# gl-gps.net
KiCad netlist of a schematic drawn in EAGLE
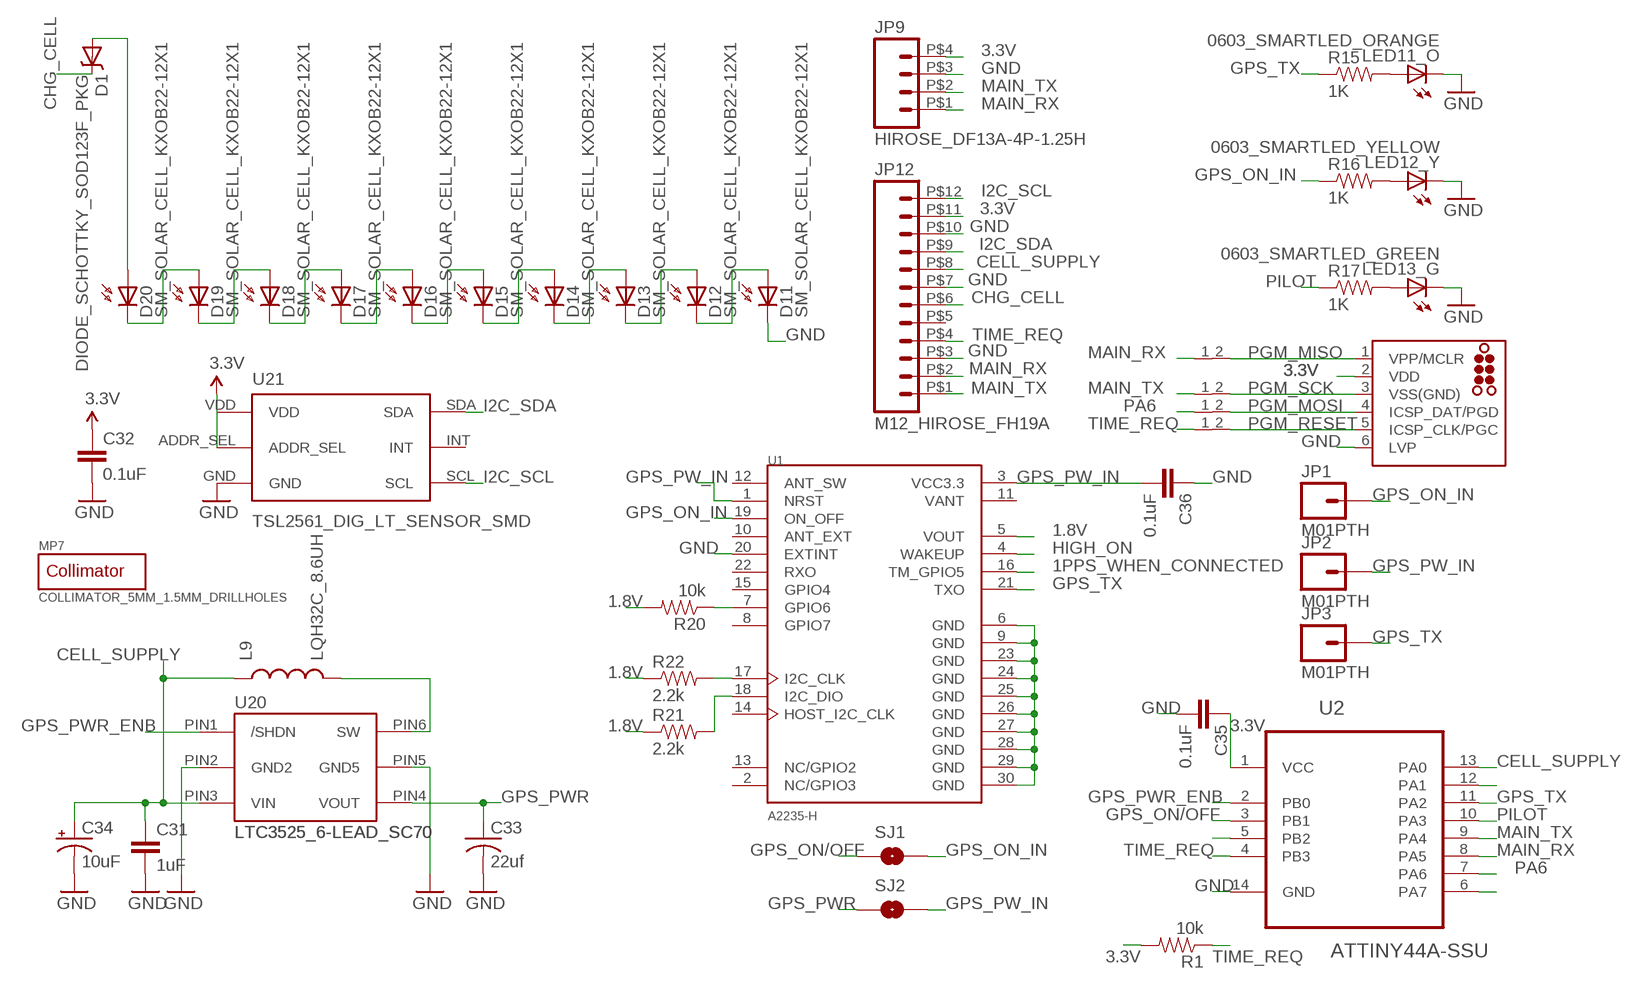
[diagram p0: schematic, sheet 1]

(export (version "E")
  (design (tool "Eeschema 10.0.6"))
  (components
    (comp (ref "C31")
      (value "1uF")
      (footprint "eagle-import:0603-CAP")
      (libsource (lib "eagle-import") (part "CAP0603-CAP"))
    )
    (comp (ref "C32")
      (value "0.1uF")
      (footprint "eagle-import:0402-CAP")
      (libsource (lib "eagle-import") (part "CAP0402-CAP"))
    )
    (comp (ref "C33")
      (value "22uf")
      (footprint "eagle-import:C1210K")
      (libsource (lib "eagle-import") (part "C-USC1210K"))
    )
    (comp (ref "C34")
      (value "10uF")
      (footprint "eagle-import:EIA3216")
      (libsource (lib "eagle-import") (part "CAP_POL1206"))
    )
    (comp (ref "C35")
      (value "0.1uF")
      (footprint "eagle-import:0402-CAP")
      (libsource (lib "eagle-import") (part "CAP0402-CAP"))
    )
    (comp (ref "C36")
      (value "0.1uF")
      (footprint "eagle-import:0402-CAP")
      (libsource (lib "eagle-import") (part "CAP0402-CAP"))
    )
    (comp (ref "D1")
      (value "DIODE_SCHOTTKY_SOD123F_PKG")
      (footprint "eagle-import:SOD123F")
      (libsource (lib "eagle-import") (part "DIODE_SCHOTTKY_SOD123F_PKG"))
    )
    (comp (ref "D11")
      (value "SM_SOLAR_CELL_KXOB22-12X1")
      (footprint "eagle-import:SM_SOLAR_CELL_KXOB22-12X1")
      (libsource (lib "eagle-import") (part "SM_SOLAR_CELL_KXOB22-12X1"))
    )
    (comp (ref "D12")
      (value "SM_SOLAR_CELL_KXOB22-12X1")
      (footprint "eagle-import:SM_SOLAR_CELL_KXOB22-12X1")
      (libsource (lib "eagle-import") (part "SM_SOLAR_CELL_KXOB22-12X1"))
    )
    (comp (ref "D13")
      (value "SM_SOLAR_CELL_KXOB22-12X1")
      (footprint "eagle-import:SM_SOLAR_CELL_KXOB22-12X1")
      (libsource (lib "eagle-import") (part "SM_SOLAR_CELL_KXOB22-12X1"))
    )
    (comp (ref "D14")
      (value "SM_SOLAR_CELL_KXOB22-12X1")
      (footprint "eagle-import:SM_SOLAR_CELL_KXOB22-12X1")
      (libsource (lib "eagle-import") (part "SM_SOLAR_CELL_KXOB22-12X1"))
    )
    (comp (ref "D15")
      (value "SM_SOLAR_CELL_KXOB22-12X1")
      (footprint "eagle-import:SM_SOLAR_CELL_KXOB22-12X1")
      (libsource (lib "eagle-import") (part "SM_SOLAR_CELL_KXOB22-12X1"))
    )
    (comp (ref "D16")
      (value "SM_SOLAR_CELL_KXOB22-12X1")
      (footprint "eagle-import:SM_SOLAR_CELL_KXOB22-12X1")
      (libsource (lib "eagle-import") (part "SM_SOLAR_CELL_KXOB22-12X1"))
    )
    (comp (ref "D17")
      (value "SM_SOLAR_CELL_KXOB22-12X1")
      (footprint "eagle-import:SM_SOLAR_CELL_KXOB22-12X1")
      (libsource (lib "eagle-import") (part "SM_SOLAR_CELL_KXOB22-12X1"))
    )
    (comp (ref "D18")
      (value "SM_SOLAR_CELL_KXOB22-12X1")
      (footprint "eagle-import:SM_SOLAR_CELL_KXOB22-12X1")
      (libsource (lib "eagle-import") (part "SM_SOLAR_CELL_KXOB22-12X1"))
    )
    (comp (ref "D19")
      (value "SM_SOLAR_CELL_KXOB22-12X1")
      (footprint "eagle-import:SM_SOLAR_CELL_KXOB22-12X1")
      (libsource (lib "eagle-import") (part "SM_SOLAR_CELL_KXOB22-12X1"))
    )
    (comp (ref "D20")
      (value "SM_SOLAR_CELL_KXOB22-12X1")
      (footprint "eagle-import:SM_SOLAR_CELL_KXOB22-12X1")
      (libsource (lib "eagle-import") (part "SM_SOLAR_CELL_KXOB22-12X1"))
    )
    (comp (ref "J1")
      (value "TC2030-MCP-NL")
      (footprint "eagle-import:TC2030-MCP-NL")
      (libsource (lib "eagle-import") (part "TC2030-MCP-NL"))
    )
    (comp (ref "JP1")
      (value "M01PTH")
      (footprint "eagle-import:1X01")
      (libsource (lib "eagle-import") (part "M01PTH"))
    )
    (comp (ref "JP2")
      (value "M01PTH")
      (footprint "eagle-import:1X01")
      (libsource (lib "eagle-import") (part "M01PTH"))
    )
    (comp (ref "JP3")
      (value "M01PTH")
      (footprint "eagle-import:1X01")
      (libsource (lib "eagle-import") (part "M01PTH"))
    )
    (comp (ref "JP9")
      (value "HIROSE_DF13A-4P-1.25H")
      (footprint "eagle-import:HIROSE_DF13A-4P-1.25H")
      (libsource (lib "eagle-import") (part "HIROSE_DF13A-4P-1.25H"))
    )
    (comp (ref "JP12")
      (value "M12_HIROSE_FH19A")
      (footprint "eagle-import:HIROSE_FH19_12POS")
      (libsource (lib "eagle-import") (part "M12_HIROSE_FH19A"))
    )
    (comp (ref "L9")
      (value "LQH32C_8.6UH")
      (footprint "eagle-import:1210_SIZE_INDUCTOR")
      (libsource (lib "eagle-import") (part "LQH32C"))
    )
    (comp (ref "LED11_O")
      (value "0603_SMARTLED_ORANGE")
      (footprint "eagle-import:0603_SMARTLED")
      (libsource (lib "eagle-import") (part "0603_SMARTLED"))
    )
    (comp (ref "LED12_Y")
      (value "0603_SMARTLED_YELLOW")
      (footprint "eagle-import:0603_SMARTLED")
      (libsource (lib "eagle-import") (part "0603_SMARTLED"))
    )
    (comp (ref "LED13_G")
      (value "0603_SMARTLED_GREEN")
      (footprint "eagle-import:0603_SMARTLED")
      (libsource (lib "eagle-import") (part "0603_SMARTLED"))
    )
    (comp (ref "MP7")
      (value "COLLIMATOR_5MM_1.5MM_DRILLHOLES")
      (footprint "eagle-import:COLLIMATOR_5MM_1.5MM_DRILLHOLES")
      (libsource (lib "eagle-import") (part "COLLIMATOR_5MM_1.5MM_DRILLHOLES"))
    )
    (comp (ref "R1")
      (value "10k")
      (footprint "eagle-import:0402-RES")
      (libsource (lib "eagle-import") (part "RESISTOR0402-RES"))
    )
    (comp (ref "R15")
      (value "1K")
      (footprint "eagle-import:0402-RES")
      (libsource (lib "eagle-import") (part "RESISTOR0402-RES"))
    )
    (comp (ref "R16")
      (value "1K")
      (footprint "eagle-import:0402-RES")
      (libsource (lib "eagle-import") (part "RESISTOR0402-RES"))
    )
    (comp (ref "R17")
      (value "1K")
      (footprint "eagle-import:0402-RES")
      (libsource (lib "eagle-import") (part "RESISTOR0402-RES"))
    )
    (comp (ref "R20")
      (value "10k")
      (footprint "eagle-import:0402-RES")
      (libsource (lib "eagle-import") (part "RESISTOR0402-RES"))
    )
    (comp (ref "R21")
      (value "2.2k")
      (footprint "eagle-import:0402-RES")
      (libsource (lib "eagle-import") (part "RESISTOR0402-RES"))
    )
    (comp (ref "R22")
      (value "2.2k")
      (footprint "eagle-import:0402-RES")
      (libsource (lib "eagle-import") (part "RESISTOR0402-RES"))
    )
    (comp (ref "SJ1")
      (value "SOLDERJUMPERTRACE")
      (footprint "eagle-import:SJ_2S-TRACE")
      (libsource (lib "eagle-import") (part "SOLDERJUMPERTRACE"))
    )
    (comp (ref "SJ2")
      (value "SOLDERJUMPERTRACE")
      (footprint "eagle-import:SJ_2S-TRACE")
      (libsource (lib "eagle-import") (part "SOLDERJUMPERTRACE"))
    )
    (comp (ref "U$2")
      (value "SHORT_8MIL8MIL")
      (footprint "eagle-import:SHORT_8MIL")
      (libsource (lib "eagle-import") (part "SHORT_8MIL8MIL"))
    )
    (comp (ref "U$3")
      (value "SHORT_8MIL8MIL")
      (footprint "eagle-import:SHORT_8MIL")
      (libsource (lib "eagle-import") (part "SHORT_8MIL8MIL"))
    )
    (comp (ref "U$4")
      (value "SHORT_8MIL8MIL")
      (footprint "eagle-import:SHORT_8MIL")
      (libsource (lib "eagle-import") (part "SHORT_8MIL8MIL"))
    )
    (comp (ref "U$5")
      (value "SHORT_8MIL8MIL")
      (footprint "eagle-import:SHORT_8MIL")
      (libsource (lib "eagle-import") (part "SHORT_8MIL8MIL"))
    )
    (comp (ref "U1")
      (value "A2235-H")
      (footprint "eagle-import:XCVR_A2235-H")
      (libsource (lib "eagle-import") (part "A2235-H"))
    )
    (comp (ref "U2")
      (value "ATTINY44A-SSU")
      (footprint "eagle-import:SOIC127P600X175-14N")
      (libsource (lib "eagle-import") (part "ATTINY44A-SSU"))
    )
    (comp (ref "U20")
      (value "LTC3525_6-LEAD_SC70")
      (footprint "eagle-import:SC70")
      (libsource (lib "eagle-import") (part "LTC3525_6-LEAD_SC70"))
    )
    (comp (ref "U21")
      (value "TSL2561_DIG_LT_SENSOR_SMD")
      (footprint "eagle-import:6_PAD_FLAT_NO-LEAD")
      (libsource (lib "eagle-import") (part "TSL2561_DIG_LT_SENSOR_SMD"))
    )
  )
  (nets
    (net (code "1") (name "/1.8V") (class "Default")
      (node (ref "R20") (pin "2") (pinfunction "2_2") (pintype "passive"))
      (node (ref "R21") (pin "1") (pinfunction "1_1") (pintype "passive"))
      (node (ref "R22") (pin "1") (pinfunction "1_1") (pintype "passive"))
      (node (ref "U1") (pin "5") (pinfunction "VOUT_5") (pintype "output"))
    )
    (net (code "2") (name "/1PPS_WHEN_CONNECTED") (class "Default")
      (node (ref "U1") (pin "16") (pinfunction "TM_GPIO5_16") (pintype "output"))
    )
    (net (code "3") (name "/CELL_SUPPLY") (class "Default")
      (node (ref "C31") (pin "1") (pinfunction "1_1") (pintype "passive"))
      (node (ref "C34") (pin "A") (pinfunction "+_A") (pintype "passive"))
      (node (ref "JP12") (pin "P$8") (pinfunction "8_P$8") (pintype "passive"))
      (node (ref "L9") (pin "P$1") (pinfunction "1_P$1") (pintype "passive"))
      (node (ref "U2") (pin "13") (pinfunction "PA0_13") (pintype "bidirectional"))
      (node (ref "U20") (pin "PIN3") (pinfunction "VIN_PIN3") (pintype "power_in"))
    )
    (net (code "4") (name "/CHG_CELL") (class "Default")
      (node (ref "D1") (pin "P$1") (pinfunction "C_P$1") (pintype "passive"))
      (node (ref "JP12") (pin "P$6") (pinfunction "6_P$6") (pintype "passive"))
    )
    (net (code "5") (name "/GPS_ON_IN") (class "Default")
      (node (ref "JP1") (pin "1") (pinfunction "1_1") (pintype "passive"))
      (node (ref "R16") (pin "1") (pinfunction "1_1") (pintype "passive"))
      (node (ref "SJ1") (pin "2") (pinfunction "2_2") (pintype "passive"))
      (node (ref "U1") (pin "19") (pinfunction "ON_OFF_19") (pintype "input"))
    )
    (net (code "6") (name "/GPS_ON{slash}OFF") (class "Default")
      (node (ref "SJ1") (pin "1") (pinfunction "1_1") (pintype "passive"))
      (node (ref "U2") (pin "3") (pinfunction "PB1_3") (pintype "bidirectional"))
    )
    (net (code "7") (name "/GPS_PWR") (class "Default")
      (node (ref "C33") (pin "1") (pinfunction "1_1") (pintype "passive"))
      (node (ref "SJ2") (pin "1") (pinfunction "1_1") (pintype "passive"))
      (node (ref "U20") (pin "PIN4") (pinfunction "VOUT_PIN4") (pintype "power_in"))
    )
    (net (code "8") (name "/GPS_PWR_ENB") (class "Default")
      (node (ref "U2") (pin "2") (pinfunction "PB0_2") (pintype "bidirectional"))
      (node (ref "U20") (pin "PIN1") (pinfunction "/SHDN_PIN1") (pintype "input"))
    )
    (net (code "9") (name "/GPS_PW_IN") (class "Default")
      (node (ref "C36") (pin "2") (pinfunction "2_2") (pintype "passive"))
      (node (ref "JP2") (pin "1") (pinfunction "1_1") (pintype "passive"))
      (node (ref "SJ2") (pin "2") (pinfunction "2_2") (pintype "passive"))
      (node (ref "U1") (pin "1") (pinfunction "NRST_1") (pintype "input"))
      (node (ref "U1") (pin "3") (pinfunction "VCC3.3_3") (pintype "power_in"))
    )
    (net (code "10") (name "/GPS_TX") (class "Default")
      (node (ref "JP3") (pin "1") (pinfunction "1_1") (pintype "passive"))
      (node (ref "R15") (pin "1") (pinfunction "1_1") (pintype "passive"))
      (node (ref "U1") (pin "21") (pinfunction "TXO_21") (pintype "output"))
      (node (ref "U2") (pin "11") (pinfunction "PA2_11") (pintype "bidirectional"))
    )
    (net (code "11") (name "/HIGH_ON") (class "Default")
      (node (ref "U1") (pin "4") (pinfunction "WAKEUP_4") (pintype "output"))
    )
    (net (code "12") (name "/I2C_SCL") (class "Default")
      (node (ref "JP12") (pin "P$12") (pinfunction "12_P$12") (pintype "passive"))
      (node (ref "U21") (pin "SCL") (pinfunction "SCL_SCL") (pintype "bidirectional"))
    )
    (net (code "13") (name "/I2C_SDA") (class "Default")
      (node (ref "JP12") (pin "P$9") (pinfunction "9_P$9") (pintype "passive"))
      (node (ref "U21") (pin "SDA") (pinfunction "SDA_SDA") (pintype "bidirectional"))
    )
    (net (code "14") (name "/MAIN_RX") (class "Default")
      (node (ref "JP12") (pin "P$2") (pinfunction "2_P$2") (pintype "passive"))
      (node (ref "JP9") (pin "P$1") (pinfunction "1_P$1") (pintype "passive"))
      (node (ref "U$2") (pin "1") (pinfunction "P_1") (pintype "bidirectional"))
      (node (ref "U2") (pin "8") (pinfunction "PA5_8") (pintype "bidirectional"))
    )
    (net (code "15") (name "/MAIN_TX") (class "Default")
      (node (ref "JP12") (pin "P$1") (pinfunction "1_P$1") (pintype "passive"))
      (node (ref "JP9") (pin "P$2") (pinfunction "2_P$2") (pintype "passive"))
      (node (ref "U$3") (pin "1") (pinfunction "P_1") (pintype "bidirectional"))
      (node (ref "U2") (pin "9") (pinfunction "PA4_9") (pintype "bidirectional"))
    )
    (net (code "16") (name "/PA6") (class "Default")
      (node (ref "U$4") (pin "1") (pinfunction "P_1") (pintype "bidirectional"))
      (node (ref "U2") (pin "7") (pinfunction "PA6_7") (pintype "bidirectional"))
    )
    (net (code "17") (name "/PGM_MISO") (class "Default")
      (node (ref "J1") (pin "1") (pinfunction "VPP/MCLR_1") (pintype "passive"))
      (node (ref "U$2") (pin "2") (pinfunction "P_2") (pintype "bidirectional"))
    )
    (net (code "18") (name "/PGM_MOSI") (class "Default")
      (node (ref "J1") (pin "4") (pinfunction "ICSP_DAT/PGD_4") (pintype "bidirectional"))
      (node (ref "U$4") (pin "2") (pinfunction "P_2") (pintype "bidirectional"))
    )
    (net (code "19") (name "/PGM_RESET") (class "Default")
      (node (ref "J1") (pin "5") (pinfunction "ICSP_CLK/PGC_5") (pintype "output"))
      (node (ref "U$5") (pin "2") (pinfunction "P_2") (pintype "bidirectional"))
    )
    (net (code "20") (name "/PGM_SCK") (class "Default")
      (node (ref "J1") (pin "3") (pinfunction "VSS(GND)_3") (pintype "power_in"))
      (node (ref "U$3") (pin "2") (pinfunction "P_2") (pintype "bidirectional"))
    )
    (net (code "21") (name "/PILOT") (class "Default")
      (node (ref "R17") (pin "1") (pinfunction "1_1") (pintype "passive"))
      (node (ref "U2") (pin "10") (pinfunction "PA3_10") (pintype "bidirectional"))
    )
    (net (code "22") (name "/TIME_REQ") (class "Default")
      (node (ref "JP12") (pin "P$4") (pinfunction "4_P$4") (pintype "passive"))
      (node (ref "R1") (pin "1") (pinfunction "1_1") (pintype "passive"))
      (node (ref "U$5") (pin "1") (pinfunction "P_1") (pintype "bidirectional"))
      (node (ref "U2") (pin "4") (pinfunction "PB3_4") (pintype "bidirectional"))
    )
    (net (code "23") (name "/VANT") (class "Default")
      (node (ref "U1") (pin "11") (pinfunction "VANT_11") (pintype "power_in"))
    )
    (net (code "24") (name "3.3V") (class "Default")
      (node (ref "C32") (pin "1") (pinfunction "1_1") (pintype "passive"))
      (node (ref "C35") (pin "1") (pinfunction "1_1") (pintype "passive"))
      (node (ref "J1") (pin "2") (pinfunction "VDD_2") (pintype "power_in"))
      (node (ref "JP12") (pin "P$11") (pinfunction "11_P$11") (pintype "passive"))
      (node (ref "JP9") (pin "P$4") (pinfunction "4_P$4") (pintype "passive"))
      (node (ref "R1") (pin "2") (pinfunction "2_2") (pintype "passive"))
      (node (ref "U2") (pin "1") (pinfunction "VCC_1") (pintype "power_in"))
      (node (ref "U21") (pin "ADDR_SEL") (pinfunction "ADDR_SEL_ADDR_SEL") (pintype "input"))
      (node (ref "U21") (pin "VDD") (pinfunction "VDD_VDD") (pintype "power_in"))
    )
    (net (code "25") (name "GND") (class "Default")
      (node (ref "C31") (pin "2") (pinfunction "2_2") (pintype "passive"))
      (node (ref "C32") (pin "2") (pinfunction "2_2") (pintype "passive"))
      (node (ref "C33") (pin "2") (pinfunction "2_2") (pintype "passive"))
      (node (ref "C34") (pin "C") (pinfunction "-_C") (pintype "passive"))
      (node (ref "C35") (pin "2") (pinfunction "2_2") (pintype "passive"))
      (node (ref "C36") (pin "1") (pinfunction "1_1") (pintype "passive"))
      (node (ref "D11") (pin "CATHODE") (pinfunction "C_CATHODE") (pintype "passive"))
      (node (ref "J1") (pin "6") (pinfunction "LVP_6") (pintype "bidirectional"))
      (node (ref "JP12") (pin "P$10") (pinfunction "10_P$10") (pintype "passive"))
      (node (ref "JP12") (pin "P$3") (pinfunction "3_P$3") (pintype "passive"))
      (node (ref "JP12") (pin "P$7") (pinfunction "7_P$7") (pintype "passive"))
      (node (ref "JP9") (pin "P$3") (pinfunction "3_P$3") (pintype "passive"))
      (node (ref "LED11_O") (pin "P$1") (pinfunction "C_P$1") (pintype "passive"))
      (node (ref "LED12_Y") (pin "P$1") (pinfunction "C_P$1") (pintype "passive"))
      (node (ref "LED13_G") (pin "P$1") (pinfunction "C_P$1") (pintype "passive"))
      (node (ref "U1") (pin "20") (pinfunction "EXTINT_20") (pintype "input"))
      (node (ref "U1") (pin "23") (pinfunction "GND_23") (pintype "power_in"))
      (node (ref "U1") (pin "24") (pinfunction "GND_24") (pintype "power_in"))
      (node (ref "U1") (pin "25") (pinfunction "GND_25") (pintype "power_in"))
      (node (ref "U1") (pin "26") (pinfunction "GND_26") (pintype "power_in"))
      (node (ref "U1") (pin "27") (pinfunction "GND_27") (pintype "power_in"))
      (node (ref "U1") (pin "28") (pinfunction "GND_28") (pintype "power_in"))
      (node (ref "U1") (pin "29") (pinfunction "GND_29") (pintype "power_in"))
      (node (ref "U1") (pin "30") (pinfunction "GND_30") (pintype "power_in"))
      (node (ref "U1") (pin "6") (pinfunction "GND_6") (pintype "power_in"))
      (node (ref "U1") (pin "9") (pinfunction "GND_9") (pintype "power_in"))
      (node (ref "U2") (pin "14") (pinfunction "GND_14") (pintype "power_in"))
      (node (ref "U20") (pin "PIN2") (pinfunction "GND2_PIN2") (pintype "power_in"))
      (node (ref "U20") (pin "PIN5") (pinfunction "GND5_PIN5") (pintype "power_in"))
      (node (ref "U21") (pin "GND") (pinfunction "GND_GND") (pintype "power_in"))
    )
    (net (code "26") (name "Net-(D1-A)") (class "Default")
      (node (ref "D1") (pin "P$2") (pinfunction "A_P$2") (pintype "passive"))
      (node (ref "D20") (pin "ANODE") (pinfunction "A_ANODE") (pintype "passive"))
    )
    (net (code "27") (name "Net-(D11-A)") (class "Default")
      (node (ref "D11") (pin "ANODE") (pinfunction "A_ANODE") (pintype "passive"))
      (node (ref "D12") (pin "CATHODE") (pinfunction "C_CATHODE") (pintype "passive"))
    )
    (net (code "28") (name "Net-(D12-A)") (class "Default")
      (node (ref "D12") (pin "ANODE") (pinfunction "A_ANODE") (pintype "passive"))
      (node (ref "D13") (pin "CATHODE") (pinfunction "C_CATHODE") (pintype "passive"))
    )
    (net (code "29") (name "Net-(D13-A)") (class "Default")
      (node (ref "D13") (pin "ANODE") (pinfunction "A_ANODE") (pintype "passive"))
      (node (ref "D14") (pin "CATHODE") (pinfunction "C_CATHODE") (pintype "passive"))
    )
    (net (code "30") (name "Net-(D14-A)") (class "Default")
      (node (ref "D14") (pin "ANODE") (pinfunction "A_ANODE") (pintype "passive"))
      (node (ref "D15") (pin "CATHODE") (pinfunction "C_CATHODE") (pintype "passive"))
    )
    (net (code "31") (name "Net-(D15-A)") (class "Default")
      (node (ref "D15") (pin "ANODE") (pinfunction "A_ANODE") (pintype "passive"))
      (node (ref "D16") (pin "CATHODE") (pinfunction "C_CATHODE") (pintype "passive"))
    )
    (net (code "32") (name "Net-(D16-A)") (class "Default")
      (node (ref "D16") (pin "ANODE") (pinfunction "A_ANODE") (pintype "passive"))
      (node (ref "D17") (pin "CATHODE") (pinfunction "C_CATHODE") (pintype "passive"))
    )
    (net (code "33") (name "Net-(D17-A)") (class "Default")
      (node (ref "D17") (pin "ANODE") (pinfunction "A_ANODE") (pintype "passive"))
      (node (ref "D18") (pin "CATHODE") (pinfunction "C_CATHODE") (pintype "passive"))
    )
    (net (code "34") (name "Net-(D18-A)") (class "Default")
      (node (ref "D18") (pin "ANODE") (pinfunction "A_ANODE") (pintype "passive"))
      (node (ref "D19") (pin "CATHODE") (pinfunction "C_CATHODE") (pintype "passive"))
    )
    (net (code "35") (name "Net-(D19-A)") (class "Default")
      (node (ref "D19") (pin "ANODE") (pinfunction "A_ANODE") (pintype "passive"))
      (node (ref "D20") (pin "CATHODE") (pinfunction "C_CATHODE") (pintype "passive"))
    )
    (net (code "36") (name "Net-(L9-2)") (class "Default")
      (node (ref "L9") (pin "P$2") (pinfunction "2_P$2") (pintype "passive"))
      (node (ref "U20") (pin "PIN6") (pinfunction "SW_PIN6") (pintype "bidirectional"))
    )
    (net (code "37") (name "Net-(LED11_O-A)") (class "Default")
      (node (ref "LED11_O") (pin "P$2") (pinfunction "A_P$2") (pintype "passive"))
      (node (ref "R15") (pin "2") (pinfunction "2_2") (pintype "passive"))
    )
    (net (code "38") (name "Net-(LED12_Y-A)") (class "Default")
      (node (ref "LED12_Y") (pin "P$2") (pinfunction "A_P$2") (pintype "passive"))
      (node (ref "R16") (pin "2") (pinfunction "2_2") (pintype "passive"))
    )
    (net (code "39") (name "Net-(LED13_G-A)") (class "Default")
      (node (ref "LED13_G") (pin "P$2") (pinfunction "A_P$2") (pintype "passive"))
      (node (ref "R17") (pin "2") (pinfunction "2_2") (pintype "passive"))
    )
    (net (code "40") (name "Net-(U1-GPIO6)") (class "Default")
      (node (ref "R20") (pin "1") (pinfunction "1_1") (pintype "passive"))
      (node (ref "U1") (pin "7") (pinfunction "GPIO6_7") (pintype "input"))
    )
    (net (code "41") (name "Net-(U1-I2C_CLK)") (class "Default")
      (node (ref "R22") (pin "2") (pinfunction "2_2") (pintype "passive"))
      (node (ref "U1") (pin "17") (pinfunction "I2C_CLK_17") (pintype "bidirectional"))
    )
    (net (code "42") (name "Net-(U1-I2C_DIO)") (class "Default")
      (node (ref "R21") (pin "2") (pinfunction "2_2") (pintype "passive"))
      (node (ref "U1") (pin "18") (pinfunction "I2C_DIO_18") (pintype "bidirectional"))
    )
    (net (code "43") (name "unconnected-(JP12-5-PadP$5)") (class "Default")
      (node (ref "JP12") (pin "P$5") (pinfunction "5_P$5") (pintype "passive"))
    )
    (net (code "44") (name "unconnected-(U1-ANT_EXT-Pad10)") (class "Default")
      (node (ref "U1") (pin "10") (pinfunction "ANT_EXT_10") (pintype "input"))
    )
    (net (code "45") (name "unconnected-(U1-ANT_SW-Pad12)") (class "Default")
      (node (ref "U1") (pin "12") (pinfunction "ANT_SW_12") (pintype "input"))
    )
    (net (code "46") (name "unconnected-(U1-GPIO4-Pad15)") (class "Default")
      (node (ref "U1") (pin "15") (pinfunction "GPIO4_15") (pintype "input"))
    )
    (net (code "47") (name "unconnected-(U1-GPIO7-Pad8)") (class "Default")
      (node (ref "U1") (pin "8") (pinfunction "GPIO7_8") (pintype "input"))
    )
    (net (code "48") (name "unconnected-(U1-HOST_I2C_CLK-Pad14)") (class "Default")
      (node (ref "U1") (pin "14") (pinfunction "HOST_I2C_CLK_14") (pintype "bidirectional"))
    )
    (net (code "49") (name "unconnected-(U1-NC{slash}GPIO2-Pad13)") (class "Default")
      (node (ref "U1") (pin "13") (pinfunction "NC/GPIO2_13") (pintype "bidirectional"))
    )
    (net (code "50") (name "unconnected-(U1-NC{slash}GPIO3-Pad2)") (class "Default")
      (node (ref "U1") (pin "2") (pinfunction "NC/GPIO3_2") (pintype "bidirectional"))
    )
    (net (code "51") (name "unconnected-(U1-RXO-Pad22)") (class "Default")
      (node (ref "U1") (pin "22") (pinfunction "RXO_22") (pintype "input"))
    )
    (net (code "52") (name "unconnected-(U2-PA1-Pad12)") (class "Default")
      (node (ref "U2") (pin "12") (pinfunction "PA1_12") (pintype "bidirectional"))
    )
    (net (code "53") (name "unconnected-(U2-PA7-Pad6)") (class "Default")
      (node (ref "U2") (pin "6") (pinfunction "PA7_6") (pintype "bidirectional"))
    )
    (net (code "54") (name "unconnected-(U2-PB2-Pad5)") (class "Default")
      (node (ref "U2") (pin "5") (pinfunction "PB2_5") (pintype "bidirectional"))
    )
    (net (code "55") (name "unconnected-(U21-PadINT)") (class "Default")
      (node (ref "U21") (pin "INT") (pinfunction "INT_INT") (pintype "output"))
    )
  )
)
